# sapflux.net
KiCad netlist of a schematic drawn in EAGLE
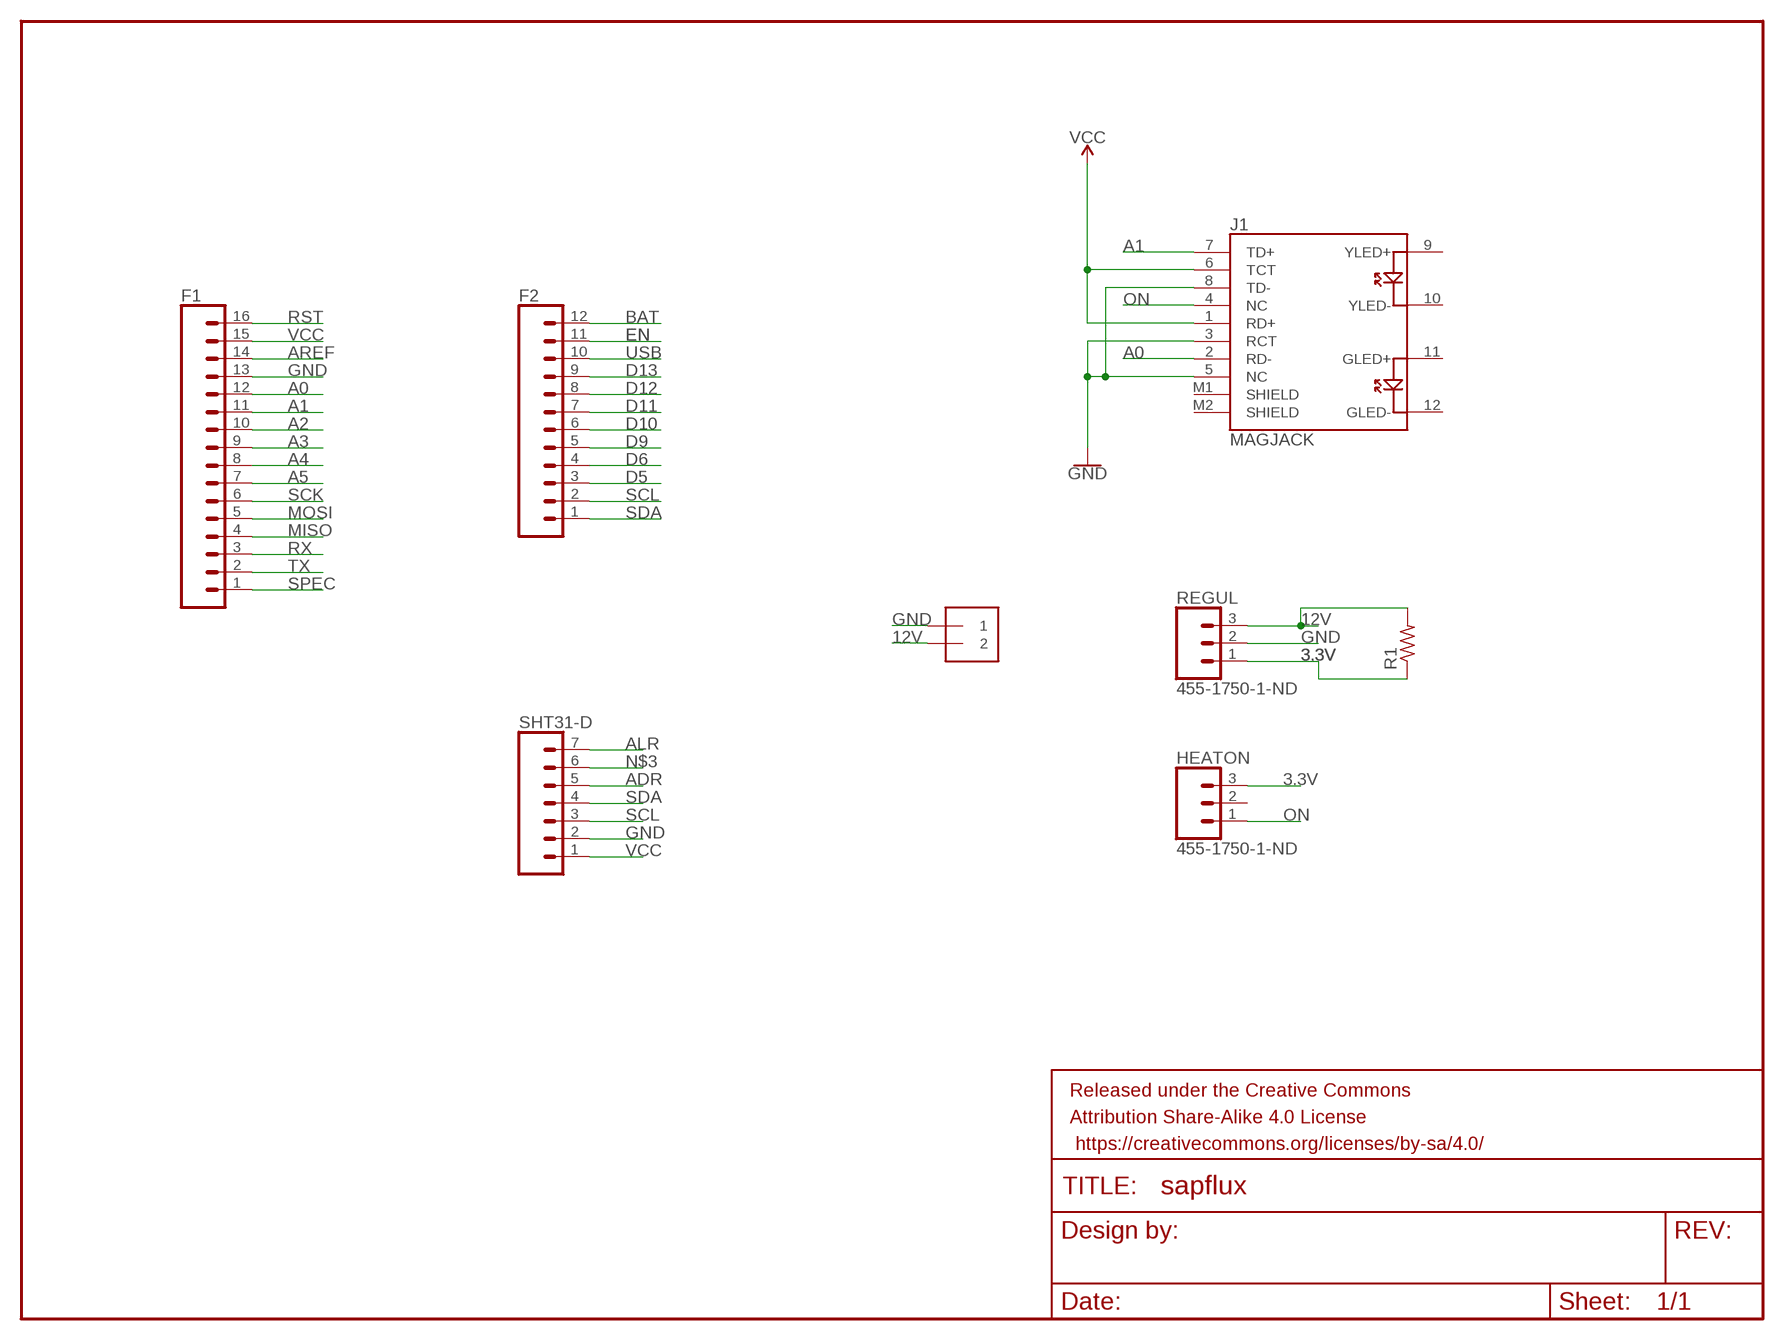
[diagram p0: schematic, sheet 1]

(export (version "E")
  (design (tool "Eeschema 10.0.6"))
  (components
    (comp (ref "F1")
      (value "CONN_16")
      (footprint "eagle-import:1X16")
      (libsource (lib "eagle-import") (part "CONN_16"))
    )
    (comp (ref "F2")
      (value "CONN_12")
      (footprint "eagle-import:1X12")
      (libsource (lib "eagle-import") (part "CONN_12"))
    )
    (comp (ref "FRAME1")
      (value "FRAME-LETTER")
      (footprint "eagle-import:CREATIVE_COMMONS")
      (libsource (lib "eagle-import") (part "FRAME-LETTER"))
    )
    (comp (ref "HEATON")
      (value "455-1750-1-ND")
      (footprint "eagle-import:1X03")
      (libsource (lib "eagle-import") (part "CONN_03"))
    )
    (comp (ref "J1")
      (value "MAGJACK")
      (footprint "eagle-import:MAGJACK")
      (libsource (lib "eagle-import") (part "MAGJACK"))
    )
    (comp (ref "J2")
      (value "1X2-3.5MM")
      (footprint "eagle-import:1X2-3.5MM")
      (libsource (lib "eagle-import") (part "1X2-3.5MM"))
    )
    (comp (ref "R1")
      (value "R-US_R0603")
      (footprint "eagle-import:R0603")
      (libsource (lib "eagle-import") (part "R-US_R0603"))
    )
    (comp (ref "REGUL")
      (value "455-1750-1-ND")
      (footprint "eagle-import:1X03")
      (libsource (lib "eagle-import") (part "CONN_03"))
    )
    (comp (ref "SHT31-D")
      (value "CONN_07")
      (footprint "eagle-import:1X07")
      (libsource (lib "eagle-import") (part "CONN_07"))
    )
  )
  (nets
    (net (code "1") (name "/3.3V") (class "Default")
      (node (ref "HEATON") (pin "3") (pinfunction "3_3") (pintype "passive"))
      (node (ref "R1") (pin "1") (pinfunction "1_1") (pintype "passive"))
      (node (ref "REGUL") (pin "1") (pinfunction "1_1") (pintype "passive"))
    )
    (net (code "2") (name "/12V") (class "Default")
      (node (ref "J2") (pin "2") (pinfunction "2_2") (pintype "passive"))
      (node (ref "R1") (pin "2") (pinfunction "2_2") (pintype "passive"))
      (node (ref "REGUL") (pin "3") (pinfunction "3_3") (pintype "passive"))
    )
    (net (code "3") (name "/A0") (class "Default")
      (node (ref "F1") (pin "12") (pinfunction "12_12") (pintype "passive"))
      (node (ref "J1") (pin "2") (pinfunction "RD-_2") (pintype "bidirectional"))
    )
    (net (code "4") (name "/A1") (class "Default")
      (node (ref "F1") (pin "11") (pinfunction "11_11") (pintype "passive"))
      (node (ref "J1") (pin "7") (pinfunction "TD+_7") (pintype "bidirectional"))
    )
    (net (code "5") (name "/A2") (class "Default")
      (node (ref "F1") (pin "10") (pinfunction "10_10") (pintype "passive"))
    )
    (net (code "6") (name "/A3") (class "Default")
      (node (ref "F1") (pin "9") (pinfunction "9_9") (pintype "passive"))
    )
    (net (code "7") (name "/A4") (class "Default")
      (node (ref "F1") (pin "8") (pinfunction "8_8") (pintype "passive"))
    )
    (net (code "8") (name "/A5") (class "Default")
      (node (ref "F1") (pin "7") (pinfunction "7_7") (pintype "passive"))
    )
    (net (code "9") (name "/ADR") (class "Default")
      (node (ref "SHT31-D") (pin "5") (pinfunction "5_5") (pintype "passive"))
    )
    (net (code "10") (name "/ALR") (class "Default")
      (node (ref "SHT31-D") (pin "7") (pinfunction "7_7") (pintype "passive"))
    )
    (net (code "11") (name "/AREF") (class "Default")
      (node (ref "F1") (pin "14") (pinfunction "14_14") (pintype "passive"))
    )
    (net (code "12") (name "/BAT") (class "Default")
      (node (ref "F2") (pin "12") (pinfunction "12_12") (pintype "passive"))
    )
    (net (code "13") (name "/D5") (class "Default")
      (node (ref "F2") (pin "3") (pinfunction "3_3") (pintype "passive"))
    )
    (net (code "14") (name "/D6") (class "Default")
      (node (ref "F2") (pin "4") (pinfunction "4_4") (pintype "passive"))
    )
    (net (code "15") (name "/D9") (class "Default")
      (node (ref "F2") (pin "5") (pinfunction "5_5") (pintype "passive"))
    )
    (net (code "16") (name "/D10") (class "Default")
      (node (ref "F2") (pin "6") (pinfunction "6_6") (pintype "passive"))
    )
    (net (code "17") (name "/D11") (class "Default")
      (node (ref "F2") (pin "7") (pinfunction "7_7") (pintype "passive"))
    )
    (net (code "18") (name "/D12") (class "Default")
      (node (ref "F2") (pin "8") (pinfunction "8_8") (pintype "passive"))
    )
    (net (code "19") (name "/D13") (class "Default")
      (node (ref "F2") (pin "9") (pinfunction "9_9") (pintype "passive"))
    )
    (net (code "20") (name "/EN") (class "Default")
      (node (ref "F2") (pin "11") (pinfunction "11_11") (pintype "passive"))
    )
    (net (code "21") (name "/MISO") (class "Default")
      (node (ref "F1") (pin "4") (pinfunction "4_4") (pintype "passive"))
    )
    (net (code "22") (name "/MOSI") (class "Default")
      (node (ref "F1") (pin "5") (pinfunction "5_5") (pintype "passive"))
    )
    (net (code "23") (name "/N$3") (class "Default")
      (node (ref "SHT31-D") (pin "6") (pinfunction "6_6") (pintype "passive"))
    )
    (net (code "24") (name "/ON") (class "Default")
      (node (ref "HEATON") (pin "1") (pinfunction "1_1") (pintype "passive"))
      (node (ref "J1") (pin "4") (pinfunction "NC_4") (pintype "bidirectional"))
    )
    (net (code "25") (name "/RST") (class "Default")
      (node (ref "F1") (pin "16") (pinfunction "16_16") (pintype "passive"))
    )
    (net (code "26") (name "/RX") (class "Default")
      (node (ref "F1") (pin "3") (pinfunction "3_3") (pintype "passive"))
    )
    (net (code "27") (name "/SCK") (class "Default")
      (node (ref "F1") (pin "6") (pinfunction "6_6") (pintype "passive"))
    )
    (net (code "28") (name "/SCL") (class "Default")
      (node (ref "F2") (pin "2") (pinfunction "2_2") (pintype "passive"))
      (node (ref "SHT31-D") (pin "3") (pinfunction "3_3") (pintype "passive"))
    )
    (net (code "29") (name "/SDA") (class "Default")
      (node (ref "F2") (pin "1") (pinfunction "1_1") (pintype "passive"))
      (node (ref "SHT31-D") (pin "4") (pinfunction "4_4") (pintype "passive"))
    )
    (net (code "30") (name "/SPEC") (class "Default")
      (node (ref "F1") (pin "1") (pinfunction "1_1") (pintype "passive"))
    )
    (net (code "31") (name "/TX") (class "Default")
      (node (ref "F1") (pin "2") (pinfunction "2_2") (pintype "passive"))
    )
    (net (code "32") (name "/USB") (class "Default")
      (node (ref "F2") (pin "10") (pinfunction "10_10") (pintype "passive"))
    )
    (net (code "33") (name "GND") (class "Default")
      (node (ref "F1") (pin "13") (pinfunction "13_13") (pintype "passive"))
      (node (ref "J1") (pin "3") (pinfunction "RCT_3") (pintype "bidirectional"))
      (node (ref "J1") (pin "5") (pinfunction "NC_5") (pintype "bidirectional"))
      (node (ref "J1") (pin "8") (pinfunction "TD-_8") (pintype "bidirectional"))
      (node (ref "J2") (pin "1") (pinfunction "1_1") (pintype "passive"))
      (node (ref "REGUL") (pin "2") (pinfunction "2_2") (pintype "passive"))
      (node (ref "SHT31-D") (pin "2") (pinfunction "2_2") (pintype "passive"))
    )
    (net (code "34") (name "VCC") (class "Default")
      (node (ref "F1") (pin "15") (pinfunction "15_15") (pintype "passive"))
      (node (ref "J1") (pin "1") (pinfunction "RD+_1") (pintype "bidirectional"))
      (node (ref "J1") (pin "6") (pinfunction "TCT_6") (pintype "bidirectional"))
      (node (ref "SHT31-D") (pin "1") (pinfunction "1_1") (pintype "passive"))
    )
    (net (code "35") (name "unconnected-(HEATON-Pad2)") (class "Default")
      (node (ref "HEATON") (pin "2") (pinfunction "2_2") (pintype "passive"))
    )
    (net (code "36") (name "unconnected-(J1-GLED+-Pad11)") (class "Default")
      (node (ref "J1") (pin "11") (pinfunction "GLED+_11") (pintype "bidirectional"))
    )
    (net (code "37") (name "unconnected-(J1-GLED--Pad12)") (class "Default")
      (node (ref "J1") (pin "12") (pinfunction "GLED-_12") (pintype "bidirectional"))
    )
    (net (code "38") (name "unconnected-(J1-SHIELD-PadM1)") (class "Default")
      (node (ref "J1") (pin "M1") (pinfunction "SHIELD_M1") (pintype "bidirectional"))
    )
    (net (code "39") (name "unconnected-(J1-SHIELD-PadM2)") (class "Default")
      (node (ref "J1") (pin "M2") (pinfunction "SHIELD_M2") (pintype "bidirectional"))
    )
    (net (code "40") (name "unconnected-(J1-YLED+-Pad9)") (class "Default")
      (node (ref "J1") (pin "9") (pinfunction "YLED+_9") (pintype "bidirectional"))
    )
    (net (code "41") (name "unconnected-(J1-YLED--Pad10)") (class "Default")
      (node (ref "J1") (pin "10") (pinfunction "YLED-_10") (pintype "bidirectional"))
    )
  )
)
